# solorTraker.net
KiCad netlist of a schematic drawn in EasyEDA Pro
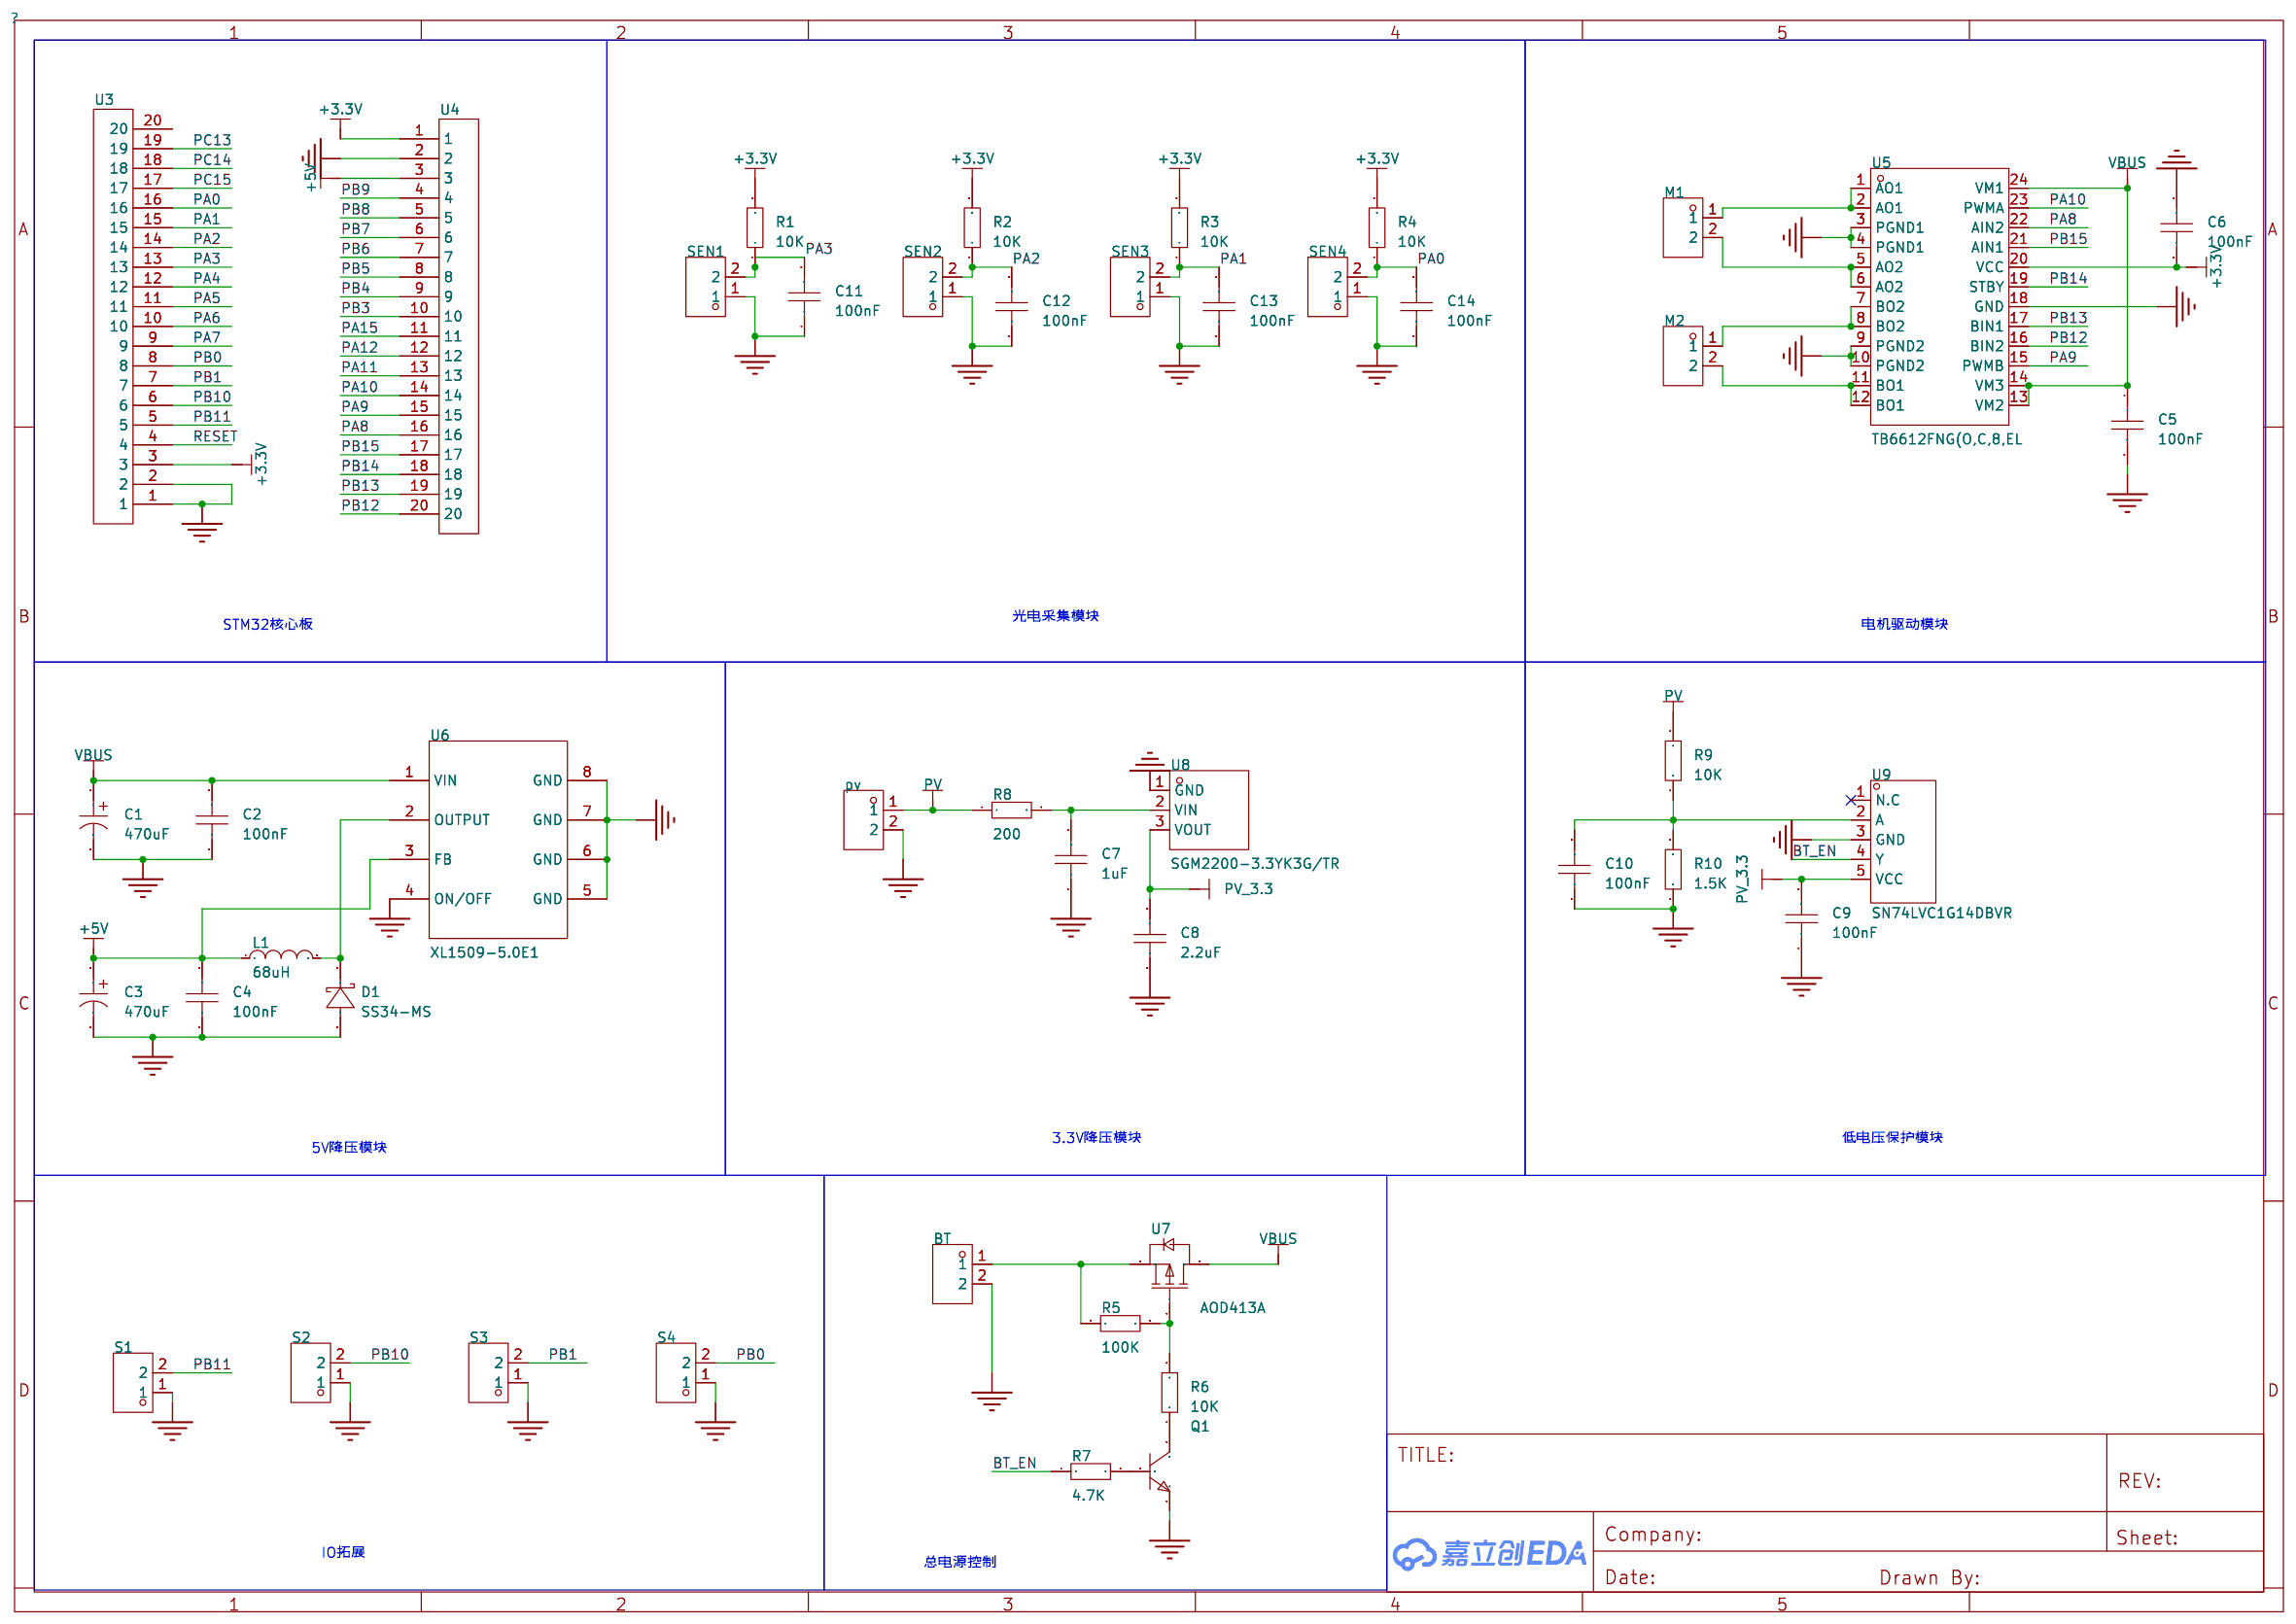
[diagram p0: schematic sheet]

(export (version "E")
  (design (tool "Eeschema 10.0.6"))
  (components
    (comp (ref "BT")
      (value "KF350-3.5-2P")
      (footprint "easyedapro:CONN-TH_P3.50_KF350-3.5-2P")
      (fields (field (name "Manufacturer") "KEFA(科发)"))
      (libsource (lib "easyedapro") (part "KF350-3.5-2P"))
    )
    (comp (ref "C1")
      (value "470uF")
      (footprint "easyedapro:CAP-SMD_BD10.0-L10.3-W10.3-LS11.0-FD")
      (description "容值:470uF;精度:±20%;额定电压:35V;纹波电流:286mA@120Hz;等效串联电阻:-;")
      (fields
        (field (name "Manufacturer Part") "RVT470UF35V67RV0056")
        (field (name "Manufacturer") "KNSCHA(科尼盛)")
      )
      (libsource (lib "easyedapro") (part "RVT470UF35V67RV0056"))
    )
    (comp (ref "C2")
      (value "100nF")
      (footprint "easyedapro:C0603")
      (libsource (lib "easyedapro") (part "CapAcitance"))
    )
    (comp (ref "C3")
      (value "470uF")
      (footprint "easyedapro:CAP-SMD_BD6.3-L6.6-W6.6-LS7.6-RD")
      (description "容值:470uF;精度:±20%;额定电压:16V;纹波电流:185mA@120Hz;")
      (fields (field (name "Manufacturer Part") "RVT1C471M0607") (field (name "Manufacturer") "ROQANG(容强)"))
      (libsource (lib "easyedapro") (part "RVT1C471M0607"))
    )
    (comp (ref "C4")
      (value "100nF")
      (footprint "easyedapro:C0603")
      (libsource (lib "easyedapro") (part "CapAcitance"))
    )
    (comp (ref "C5")
      (value "100nF")
      (footprint "easyedapro:C0603")
      (libsource (lib "easyedapro") (part "CapAcitance"))
    )
    (comp (ref "C6")
      (value "100nF")
      (footprint "easyedapro:C0603")
      (libsource (lib "easyedapro") (part "CapAcitance"))
    )
    (comp (ref "C7")
      (value "1uF")
      (footprint "easyedapro:C0603")
      (libsource (lib "easyedapro") (part "CapAcitance"))
    )
    (comp (ref "C8")
      (value "2.2uF")
      (footprint "easyedapro:C0603")
      (libsource (lib "easyedapro") (part "CapAcitance"))
    )
    (comp (ref "C9")
      (value "100nF")
      (footprint "easyedapro:C0603")
      (libsource (lib "easyedapro") (part "CapAcitance"))
    )
    (comp (ref "C10")
      (value "100nF")
      (footprint "easyedapro:C0603")
      (libsource (lib "easyedapro") (part "CapAcitance"))
    )
    (comp (ref "C11")
      (value "100nF")
      (footprint "easyedapro:C0603")
      (libsource (lib "easyedapro") (part "CapAcitance"))
    )
    (comp (ref "C12")
      (value "100nF")
      (footprint "easyedapro:C0603")
      (libsource (lib "easyedapro") (part "CapAcitance"))
    )
    (comp (ref "C13")
      (value "100nF")
      (footprint "easyedapro:C0603")
      (libsource (lib "easyedapro") (part "CapAcitance"))
    )
    (comp (ref "C14")
      (value "100nF")
      (footprint "easyedapro:C0603")
      (libsource (lib "easyedapro") (part "CapAcitance"))
    )
    (comp (ref "D1")
      (value "SS34-MS")
      (footprint "easyedapro:DO-214AC_L4.3-W2.7-LS5.0-RD")
      (description "二极管配置:-;正向压降(Vf):550mV@3A;直流反向耐压(Vr):40V;平均整流电流(Io):3A;")
      (fields (field (name "Manufacturer") "MSKSEMI(美森科)"))
      (libsource (lib "easyedapro") (part "SS34-MS"))
    )
    (comp (ref "L1")
      (value "68uH")
      (footprint "easyedapro:IND-SMD_L11.5-W10.0_104CDMCCDS")
      (description "电感值:68uH;精度:±20%;额定电流:2.5A;饱和电流(Isat):3A;类型:一体成型电感;")
      (fields (field (name "Manufacturer Part") "FXL1040-680-M") (field (name "Manufacturer") "cjiang(长江微电)"))
      (libsource (lib "easyedapro") (part "FXL1040-680-M"))
    )
    (comp (ref "M1")
      (value "ZX-XH2.54-2PZZ")
      (footprint "easyedapro:CONN-TH_2P-P2.50_HX25003-2A")
      (fields (field (name "Manufacturer") "Megastar(兆星)"))
      (libsource (lib "easyedapro") (part "ZX-XH2.54-2PZZ"))
    )
    (comp (ref "M2")
      (value "ZX-XH2.54-2PZZ")
      (footprint "easyedapro:CONN-TH_2P-P2.50_HX25003-2A")
      (fields (field (name "Manufacturer") "Megastar(兆星)"))
      (libsource (lib "easyedapro") (part "ZX-XH2.54-2PZZ"))
    )
    (comp (ref "pv")
      (value "ZX-XH2.54-2PZZ")
      (footprint "easyedapro:CONN-TH_2P-P2.50_HX25003-2A")
      (fields (field (name "Manufacturer") "Megastar(兆星)"))
      (libsource (lib "easyedapro") (part "ZX-XH2.54-2PZZ"))
    )
    (comp (ref "Q1")
      (value "~")
      (footprint "easyedapro:S8050_SOT-23")
      (libsource (lib "easyedapro") (part "NPN"))
    )
    (comp (ref "R1") (value "10K") (footprint "easyedapro:R0603") (libsource (lib "easyedapro") (part "电阻")))
    (comp (ref "R2") (value "10K") (footprint "easyedapro:R0603") (libsource (lib "easyedapro") (part "电阻")))
    (comp (ref "R3") (value "10K") (footprint "easyedapro:R0603") (libsource (lib "easyedapro") (part "电阻")))
    (comp (ref "R4") (value "10K") (footprint "easyedapro:R0603") (libsource (lib "easyedapro") (part "电阻")))
    (comp (ref "R5") (value "100K") (footprint "easyedapro:R0603") (libsource (lib "easyedapro") (part "电阻")))
    (comp (ref "R6") (value "10K") (footprint "easyedapro:R0603") (libsource (lib "easyedapro") (part "电阻")))
    (comp (ref "R7") (value "4.7K") (footprint "easyedapro:R0603") (libsource (lib "easyedapro") (part "电阻")))
    (comp (ref "R8") (value "200") (footprint "easyedapro:R0603") (libsource (lib "easyedapro") (part "电阻")))
    (comp (ref "R9") (value "10K") (footprint "easyedapro:R0603") (libsource (lib "easyedapro") (part "电阻")))
    (comp (ref "R10")
      (value "1.5K")
      (footprint "easyedapro:R0603")
      (libsource (lib "easyedapro") (part "电阻"))
    )
    (comp (ref "S1")
      (value "ZX-XH2.54-2PZZ")
      (footprint "easyedapro:CONN-TH_2P-P2.50_HX25003-2A")
      (fields (field (name "Manufacturer") "Megastar(兆星)"))
      (libsource (lib "easyedapro") (part "ZX-XH2.54-2PZZ"))
    )
    (comp (ref "S2")
      (value "ZX-XH2.54-2PZZ")
      (footprint "easyedapro:CONN-TH_2P-P2.50_HX25003-2A")
      (fields (field (name "Manufacturer") "Megastar(兆星)"))
      (libsource (lib "easyedapro") (part "ZX-XH2.54-2PZZ"))
    )
    (comp (ref "S3")
      (value "ZX-XH2.54-2PZZ")
      (footprint "easyedapro:CONN-TH_2P-P2.50_HX25003-2A")
      (fields (field (name "Manufacturer") "Megastar(兆星)"))
      (libsource (lib "easyedapro") (part "ZX-XH2.54-2PZZ"))
    )
    (comp (ref "S4")
      (value "ZX-XH2.54-2PZZ")
      (footprint "easyedapro:CONN-TH_2P-P2.50_HX25003-2A")
      (fields (field (name "Manufacturer") "Megastar(兆星)"))
      (libsource (lib "easyedapro") (part "ZX-XH2.54-2PZZ"))
    )
    (comp (ref "SEN1")
      (value "ZX-XH2.54-2PZZ")
      (footprint "easyedapro:CONN-TH_2P-P2.50_HX25003-2A")
      (fields (field (name "Manufacturer") "Megastar(兆星)"))
      (libsource (lib "easyedapro") (part "ZX-XH2.54-2PZZ"))
    )
    (comp (ref "SEN2")
      (value "ZX-XH2.54-2PZZ")
      (footprint "easyedapro:CONN-TH_2P-P2.50_HX25003-2A")
      (fields (field (name "Manufacturer") "Megastar(兆星)"))
      (libsource (lib "easyedapro") (part "ZX-XH2.54-2PZZ"))
    )
    (comp (ref "SEN3")
      (value "ZX-XH2.54-2PZZ")
      (footprint "easyedapro:CONN-TH_2P-P2.50_HX25003-2A")
      (fields (field (name "Manufacturer") "Megastar(兆星)"))
      (libsource (lib "easyedapro") (part "ZX-XH2.54-2PZZ"))
    )
    (comp (ref "SEN4")
      (value "ZX-XH2.54-2PZZ")
      (footprint "easyedapro:CONN-TH_2P-P2.50_HX25003-2A")
      (fields (field (name "Manufacturer") "Megastar(兆星)"))
      (libsource (lib "easyedapro") (part "ZX-XH2.54-2PZZ"))
    )
    (comp (ref "U3")
      (value "~")
      (footprint "easyedapro:HDR1X20")
      (libsource (lib "easyedapro") (part "1X20"))
    )
    (comp (ref "U4")
      (value "~")
      (footprint "easyedapro:HDR1X20")
      (libsource (lib "easyedapro") (part "1X20"))
    )
    (comp (ref "U5")
      (value "TB6612FNG(O,C,8,EL")
      (footprint "easyedapro:SSOP-24_L8.4-W5.8-P0.65-LS7.8-BL")
      (description "双直流电机驱动器集成电路")
      (fields (field (name "Manufacturer") "TOSHIBA(东芝)"))
      (libsource (lib "easyedapro") (part "TB6612FNG(O,C,8,EL"))
    )
    (comp (ref "U6")
      (value "XL1509-5.0E1")
      (footprint "easyedapro:SOIC-8_L5.0-W4.0-P1.27-LS6.0-BL")
      (description "功能类型:降压型;输入电压:-;输出电流(最大值):-;")
      (fields (field (name "Manufacturer") "XLSEMI(芯龙)"))
      (libsource (lib "easyedapro") (part "XL1509-5.0E1"))
    )
    (comp (ref "U7")
      (value "AOD413A")
      (footprint "easyedapro:TO-252-2_L6.6-W6.1-P4.58-LS10.1-BR-CW")
      (fields (field (name "Manufacturer") "HXY MOSFET(华轩阳电子)"))
      (libsource (lib "easyedapro") (part "AOD413A_C5261059"))
    )
    (comp (ref "U8")
      (value "SGM2200-3.3YK3G/TR")
      (footprint "easyedapro:SOT-89-3_L4.5-W2.5-P1.50-LS4.2-BR")
      (fields (field (name "Manufacturer") "SGMICRO(圣邦微)"))
      (libsource (lib "easyedapro") (part "SGM2200-3.3YK3G/TR"))
    )
    (comp (ref "U9")
      (value "SN74LVC1G14DBVR")
      (footprint "easyedapro:SOT-23-5_L3.0-W1.7-P0.95-LS2.8-BR")
      (description "输入类型:施密特触发器;电源电压:1.65V~5.5V;供电电流(最大值):10uA;电路数:1;最大传播延迟(tpd):6.5ns@2.5V,50pF;")
      (fields (field (name "Manufacturer") "TI(德州仪器)"))
      (libsource (lib "easyedapro") (part "SN74LVC1G14DBVR"))
    )
  )
  (nets
    (net (code "1") (name "+3.3V") (class "Default")
      (node (ref "C6") (pin "2") (pinfunction "2_2") (pintype "input"))
      (node (ref "R1") (pin "2") (pinfunction "2_2") (pintype "input"))
      (node (ref "R2") (pin "2") (pinfunction "2_2") (pintype "input"))
      (node (ref "R3") (pin "2") (pinfunction "2_2") (pintype "input"))
      (node (ref "R4") (pin "2") (pinfunction "2_2") (pintype "input"))
      (node (ref "U3") (pin "3") (pinfunction "3_3") (pintype "input"))
      (node (ref "U4") (pin "1") (pinfunction "1_1") (pintype "input"))
      (node (ref "U5") (pin "20") (pinfunction "VCC_20") (pintype "unspecified"))
    )
    (net (code "2") (name "+5V") (class "Default")
      (node (ref "C3") (pin "1") (pinfunction "1_1") (pintype "input"))
      (node (ref "C4") (pin "2") (pinfunction "2_2") (pintype "input"))
      (node (ref "L1") (pin "1") (pinfunction "1_1") (pintype "unspecified"))
      (node (ref "U4") (pin "3") (pinfunction "3_3") (pintype "input"))
      (node (ref "U6") (pin "3") (pinfunction "FB_3") (pintype "unspecified"))
    )
    (net (code "3") (name "/BT_EN") (class "Default")
      (node (ref "R7") (pin "1") (pinfunction "1_1") (pintype "input"))
      (node (ref "U9") (pin "4") (pinfunction "Y_4") (pintype "unspecified"))
    )
    (net (code "4") (name "/PA0") (class "Default")
      (node (ref "C14") (pin "2") (pinfunction "2_2") (pintype "input"))
      (node (ref "R4") (pin "1") (pinfunction "1_1") (pintype "input"))
      (node (ref "SEN4") (pin "2") (pinfunction "2_2") (pintype "unspecified"))
      (node (ref "U3") (pin "16") (pinfunction "16_16") (pintype "input"))
    )
    (net (code "5") (name "/PA1") (class "Default")
      (node (ref "C13") (pin "2") (pinfunction "2_2") (pintype "input"))
      (node (ref "R3") (pin "1") (pinfunction "1_1") (pintype "input"))
      (node (ref "SEN3") (pin "2") (pinfunction "2_2") (pintype "unspecified"))
      (node (ref "U3") (pin "15") (pinfunction "15_15") (pintype "input"))
    )
    (net (code "6") (name "/PA2") (class "Default")
      (node (ref "C12") (pin "2") (pinfunction "2_2") (pintype "input"))
      (node (ref "R2") (pin "1") (pinfunction "1_1") (pintype "input"))
      (node (ref "SEN2") (pin "2") (pinfunction "2_2") (pintype "unspecified"))
      (node (ref "U3") (pin "14") (pinfunction "14_14") (pintype "input"))
    )
    (net (code "7") (name "/PA3") (class "Default")
      (node (ref "C11") (pin "2") (pinfunction "2_2") (pintype "input"))
      (node (ref "R1") (pin "1") (pinfunction "1_1") (pintype "input"))
      (node (ref "SEN1") (pin "2") (pinfunction "2_2") (pintype "unspecified"))
      (node (ref "U3") (pin "13") (pinfunction "13_13") (pintype "input"))
    )
    (net (code "8") (name "/PA4") (class "Default")
      (node (ref "U3") (pin "12") (pinfunction "12_12") (pintype "input"))
    )
    (net (code "9") (name "/PA5") (class "Default")
      (node (ref "U3") (pin "11") (pinfunction "11_11") (pintype "input"))
    )
    (net (code "10") (name "/PA6") (class "Default")
      (node (ref "U3") (pin "10") (pinfunction "10_10") (pintype "input"))
    )
    (net (code "11") (name "/PA7") (class "Default")
      (node (ref "U3") (pin "9") (pinfunction "9_9") (pintype "input"))
    )
    (net (code "12") (name "/PA8") (class "Default")
      (node (ref "U4") (pin "16") (pinfunction "16_16") (pintype "input"))
      (node (ref "U5") (pin "22") (pinfunction "AIN2_22") (pintype "unspecified"))
    )
    (net (code "13") (name "/PA9") (class "Default")
      (node (ref "U4") (pin "15") (pinfunction "15_15") (pintype "input"))
      (node (ref "U5") (pin "15") (pinfunction "PWMB_15") (pintype "unspecified"))
    )
    (net (code "14") (name "/PA10") (class "Default")
      (node (ref "U4") (pin "14") (pinfunction "14_14") (pintype "input"))
      (node (ref "U5") (pin "23") (pinfunction "PWMA_23") (pintype "unspecified"))
    )
    (net (code "15") (name "/PA11") (class "Default")
      (node (ref "U4") (pin "13") (pinfunction "13_13") (pintype "input"))
    )
    (net (code "16") (name "/PA12") (class "Default")
      (node (ref "U4") (pin "12") (pinfunction "12_12") (pintype "input"))
    )
    (net (code "17") (name "/PA15") (class "Default")
      (node (ref "U4") (pin "11") (pinfunction "11_11") (pintype "input"))
    )
    (net (code "18") (name "/PB0") (class "Default")
      (node (ref "S4") (pin "2") (pinfunction "2_2") (pintype "unspecified"))
      (node (ref "U3") (pin "8") (pinfunction "8_8") (pintype "input"))
    )
    (net (code "19") (name "/PB1") (class "Default")
      (node (ref "S3") (pin "2") (pinfunction "2_2") (pintype "unspecified"))
      (node (ref "U3") (pin "7") (pinfunction "7_7") (pintype "input"))
    )
    (net (code "20") (name "/PB3") (class "Default")
      (node (ref "U4") (pin "10") (pinfunction "10_10") (pintype "input"))
    )
    (net (code "21") (name "/PB4") (class "Default")
      (node (ref "U4") (pin "9") (pinfunction "9_9") (pintype "input"))
    )
    (net (code "22") (name "/PB5") (class "Default")
      (node (ref "U4") (pin "8") (pinfunction "8_8") (pintype "input"))
    )
    (net (code "23") (name "/PB6") (class "Default")
      (node (ref "U4") (pin "7") (pinfunction "7_7") (pintype "input"))
    )
    (net (code "24") (name "/PB7") (class "Default")
      (node (ref "U4") (pin "6") (pinfunction "6_6") (pintype "input"))
    )
    (net (code "25") (name "/PB8") (class "Default")
      (node (ref "U4") (pin "5") (pinfunction "5_5") (pintype "input"))
    )
    (net (code "26") (name "/PB9") (class "Default")
      (node (ref "U4") (pin "4") (pinfunction "4_4") (pintype "input"))
    )
    (net (code "27") (name "/PB10") (class "Default")
      (node (ref "S2") (pin "2") (pinfunction "2_2") (pintype "unspecified"))
      (node (ref "U3") (pin "6") (pinfunction "6_6") (pintype "input"))
    )
    (net (code "28") (name "/PB11") (class "Default")
      (node (ref "S1") (pin "2") (pinfunction "2_2") (pintype "unspecified"))
      (node (ref "U3") (pin "5") (pinfunction "5_5") (pintype "input"))
    )
    (net (code "29") (name "/PB12") (class "Default")
      (node (ref "U4") (pin "20") (pinfunction "20_20") (pintype "input"))
      (node (ref "U5") (pin "16") (pinfunction "BIN2_16") (pintype "unspecified"))
    )
    (net (code "30") (name "/PB13") (class "Default")
      (node (ref "U4") (pin "19") (pinfunction "19_19") (pintype "input"))
      (node (ref "U5") (pin "17") (pinfunction "BIN1_17") (pintype "unspecified"))
    )
    (net (code "31") (name "/PB14") (class "Default")
      (node (ref "U4") (pin "18") (pinfunction "18_18") (pintype "input"))
      (node (ref "U5") (pin "19") (pinfunction "STBY_19") (pintype "unspecified"))
    )
    (net (code "32") (name "/PB15") (class "Default")
      (node (ref "U4") (pin "17") (pinfunction "17_17") (pintype "input"))
      (node (ref "U5") (pin "21") (pinfunction "AIN1_21") (pintype "unspecified"))
    )
    (net (code "33") (name "/PC13") (class "Default")
      (node (ref "U3") (pin "19") (pinfunction "19_19") (pintype "input"))
    )
    (net (code "34") (name "/PC14") (class "Default")
      (node (ref "U3") (pin "18") (pinfunction "18_18") (pintype "input"))
    )
    (net (code "35") (name "/PC15") (class "Default")
      (node (ref "U3") (pin "17") (pinfunction "17_17") (pintype "input"))
    )
    (net (code "36") (name "/RESET") (class "Default")
      (node (ref "U3") (pin "4") (pinfunction "4_4") (pintype "input"))
    )
    (net (code "37") (name "GND") (class "Default")
      (node (ref "BT") (pin "2") (pinfunction "2_2") (pintype "unspecified"))
      (node (ref "C1") (pin "2") (pinfunction "2_2") (pintype "input"))
      (node (ref "C10") (pin "1") (pinfunction "1_1") (pintype "input"))
      (node (ref "C11") (pin "1") (pinfunction "1_1") (pintype "input"))
      (node (ref "C12") (pin "1") (pinfunction "1_1") (pintype "input"))
      (node (ref "C13") (pin "1") (pinfunction "1_1") (pintype "input"))
      (node (ref "C14") (pin "1") (pinfunction "1_1") (pintype "input"))
      (node (ref "C2") (pin "1") (pinfunction "1_1") (pintype "input"))
      (node (ref "C3") (pin "2") (pinfunction "2_2") (pintype "input"))
      (node (ref "C4") (pin "1") (pinfunction "1_1") (pintype "input"))
      (node (ref "C5") (pin "2") (pinfunction "2_2") (pintype "input"))
      (node (ref "C6") (pin "1") (pinfunction "1_1") (pintype "input"))
      (node (ref "C7") (pin "1") (pinfunction "1_1") (pintype "input"))
      (node (ref "C8") (pin "1") (pinfunction "1_1") (pintype "input"))
      (node (ref "C9") (pin "1") (pinfunction "1_1") (pintype "input"))
      (node (ref "D1") (pin "2") (pinfunction "K_2") (pintype "unspecified"))
      (node (ref "Q1") (pin "2") (pinfunction "2_2") (pintype "unspecified"))
      (node (ref "R10") (pin "1") (pinfunction "1_1") (pintype "input"))
      (node (ref "S1") (pin "1") (pinfunction "1_1") (pintype "unspecified"))
      (node (ref "S2") (pin "1") (pinfunction "1_1") (pintype "unspecified"))
      (node (ref "S3") (pin "1") (pinfunction "1_1") (pintype "unspecified"))
      (node (ref "S4") (pin "1") (pinfunction "1_1") (pintype "unspecified"))
      (node (ref "SEN1") (pin "1") (pinfunction "1_1") (pintype "unspecified"))
      (node (ref "SEN2") (pin "1") (pinfunction "1_1") (pintype "unspecified"))
      (node (ref "SEN3") (pin "1") (pinfunction "1_1") (pintype "unspecified"))
      (node (ref "SEN4") (pin "1") (pinfunction "1_1") (pintype "unspecified"))
      (node (ref "U3") (pin "1") (pinfunction "1_1") (pintype "input"))
      (node (ref "U3") (pin "2") (pinfunction "2_2") (pintype "input"))
      (node (ref "U4") (pin "2") (pinfunction "2_2") (pintype "input"))
      (node (ref "U5") (pin "10") (pinfunction "PGND2_10") (pintype "unspecified"))
      (node (ref "U5") (pin "18") (pinfunction "GND_18") (pintype "unspecified"))
      (node (ref "U5") (pin "3") (pinfunction "PGND1_3") (pintype "unspecified"))
      (node (ref "U5") (pin "4") (pinfunction "PGND1_4") (pintype "unspecified"))
      (node (ref "U5") (pin "9") (pinfunction "PGND2_9") (pintype "unspecified"))
      (node (ref "U6") (pin "4") (pinfunction "ON/OFF_4") (pintype "unspecified"))
      (node (ref "U6") (pin "5") (pinfunction "GND_5") (pintype "unspecified"))
      (node (ref "U6") (pin "6") (pinfunction "GND_6") (pintype "unspecified"))
      (node (ref "U6") (pin "7") (pinfunction "GND_7") (pintype "unspecified"))
      (node (ref "U6") (pin "8") (pinfunction "GND_8") (pintype "unspecified"))
      (node (ref "U8") (pin "1") (pinfunction "GND_1") (pintype "unspecified"))
      (node (ref "U9") (pin "3") (pinfunction "GND_3") (pintype "unspecified"))
      (node (ref "pv") (pin "2") (pinfunction "2_2") (pintype "unspecified"))
    )
    (net (code "38") (name "Net-(D1-A)") (class "Default")
      (node (ref "D1") (pin "1") (pinfunction "A_1") (pintype "unspecified"))
      (node (ref "L1") (pin "2") (pinfunction "2_2") (pintype "unspecified"))
      (node (ref "U6") (pin "2") (pinfunction "OUTPUT_2") (pintype "unspecified"))
    )
    (net (code "39") (name "Net-(M1-Pad1)") (class "Default")
      (node (ref "M1") (pin "1") (pinfunction "1_1") (pintype "unspecified"))
      (node (ref "U5") (pin "1") (pinfunction "AO1_1") (pintype "unspecified"))
      (node (ref "U5") (pin "2") (pinfunction "AO1_2") (pintype "unspecified"))
    )
    (net (code "40") (name "Net-(M1-Pad2)") (class "Default")
      (node (ref "M1") (pin "2") (pinfunction "2_2") (pintype "unspecified"))
      (node (ref "U5") (pin "5") (pinfunction "AO2_5") (pintype "unspecified"))
      (node (ref "U5") (pin "6") (pinfunction "AO2_6") (pintype "unspecified"))
    )
    (net (code "41") (name "Net-(M2-Pad1)") (class "Default")
      (node (ref "M2") (pin "1") (pinfunction "1_1") (pintype "unspecified"))
      (node (ref "U5") (pin "7") (pinfunction "BO2_7") (pintype "unspecified"))
      (node (ref "U5") (pin "8") (pinfunction "BO2_8") (pintype "unspecified"))
    )
    (net (code "42") (name "Net-(M2-Pad2)") (class "Default")
      (node (ref "M2") (pin "2") (pinfunction "2_2") (pintype "unspecified"))
      (node (ref "U5") (pin "11") (pinfunction "BO1_11") (pintype "unspecified"))
      (node (ref "U5") (pin "12") (pinfunction "BO1_12") (pintype "unspecified"))
    )
    (net (code "43") (name "Net-(Q1-Pad1)") (class "Default")
      (node (ref "Q1") (pin "1") (pinfunction "1_1") (pintype "unspecified"))
      (node (ref "R7") (pin "2") (pinfunction "2_2") (pintype "input"))
    )
    (net (code "44") (name "Net-(Q1-Pad3)") (class "Default")
      (node (ref "Q1") (pin "3") (pinfunction "3_3") (pintype "unspecified"))
      (node (ref "R6") (pin "1") (pinfunction "1_1") (pintype "input"))
    )
    (net (code "45") (name "Net-(U7-G)") (class "Default")
      (node (ref "R5") (pin "2") (pinfunction "2_2") (pintype "input"))
      (node (ref "R6") (pin "2") (pinfunction "2_2") (pintype "input"))
      (node (ref "U7") (pin "1") (pinfunction "G_1") (pintype "unspecified"))
    )
    (net (code "46") (name "Net-(U7-S)") (class "Default")
      (node (ref "BT") (pin "1") (pinfunction "1_1") (pintype "unspecified"))
      (node (ref "R5") (pin "1") (pinfunction "1_1") (pintype "input"))
      (node (ref "U7") (pin "3") (pinfunction "S_3") (pintype "unspecified"))
    )
    (net (code "47") (name "Net-(U8-VIN)") (class "Default")
      (node (ref "C7") (pin "2") (pinfunction "2_2") (pintype "input"))
      (node (ref "R8") (pin "2") (pinfunction "2_2") (pintype "input"))
      (node (ref "U8") (pin "2") (pinfunction "VIN_2") (pintype "unspecified"))
    )
    (net (code "48") (name "Net-(U9-A)") (class "Default")
      (node (ref "C10") (pin "2") (pinfunction "2_2") (pintype "input"))
      (node (ref "R10") (pin "2") (pinfunction "2_2") (pintype "input"))
      (node (ref "R9") (pin "1") (pinfunction "1_1") (pintype "input"))
      (node (ref "U9") (pin "2") (pinfunction "A_2") (pintype "unspecified"))
    )
    (net (code "49") (name "PV") (class "Default")
      (node (ref "R8") (pin "1") (pinfunction "1_1") (pintype "input"))
      (node (ref "R9") (pin "2") (pinfunction "2_2") (pintype "input"))
      (node (ref "pv") (pin "1") (pinfunction "1_1") (pintype "unspecified"))
    )
    (net (code "50") (name "PV_3.3") (class "Default")
      (node (ref "C8") (pin "2") (pinfunction "2_2") (pintype "input"))
      (node (ref "C9") (pin "2") (pinfunction "2_2") (pintype "input"))
      (node (ref "U8") (pin "3") (pinfunction "VOUT_3") (pintype "unspecified"))
      (node (ref "U9") (pin "5") (pinfunction "VCC_5") (pintype "unspecified"))
    )
    (net (code "51") (name "VBUS") (class "Default")
      (node (ref "C1") (pin "1") (pinfunction "1_1") (pintype "input"))
      (node (ref "C2") (pin "2") (pinfunction "2_2") (pintype "input"))
      (node (ref "C5") (pin "1") (pinfunction "1_1") (pintype "input"))
      (node (ref "U5") (pin "13") (pinfunction "VM2_13") (pintype "unspecified"))
      (node (ref "U5") (pin "14") (pinfunction "VM3_14") (pintype "unspecified"))
      (node (ref "U5") (pin "24") (pinfunction "VM1_24") (pintype "unspecified"))
      (node (ref "U6") (pin "1") (pinfunction "VIN_1") (pintype "unspecified"))
      (node (ref "U7") (pin "2") (pinfunction "D_2") (pintype "unspecified"))
    )
    (net (code "52") (name "unconnected-(U3-Pad20)") (class "Default")
      (node (ref "U3") (pin "20") (pinfunction "20_20") (pintype "input"))
    )
    (net (code "53") (name "unconnected-(U9-N.C-Pad1)") (class "Default")
      (node (ref "U9") (pin "1") (pinfunction "N.C_1") (pintype "unspecified+no_connect"))
    )
  )
)
